# Two_Nine_Five_Rev_1.net
KiCad netlist of a schematic drawn in EAGLE
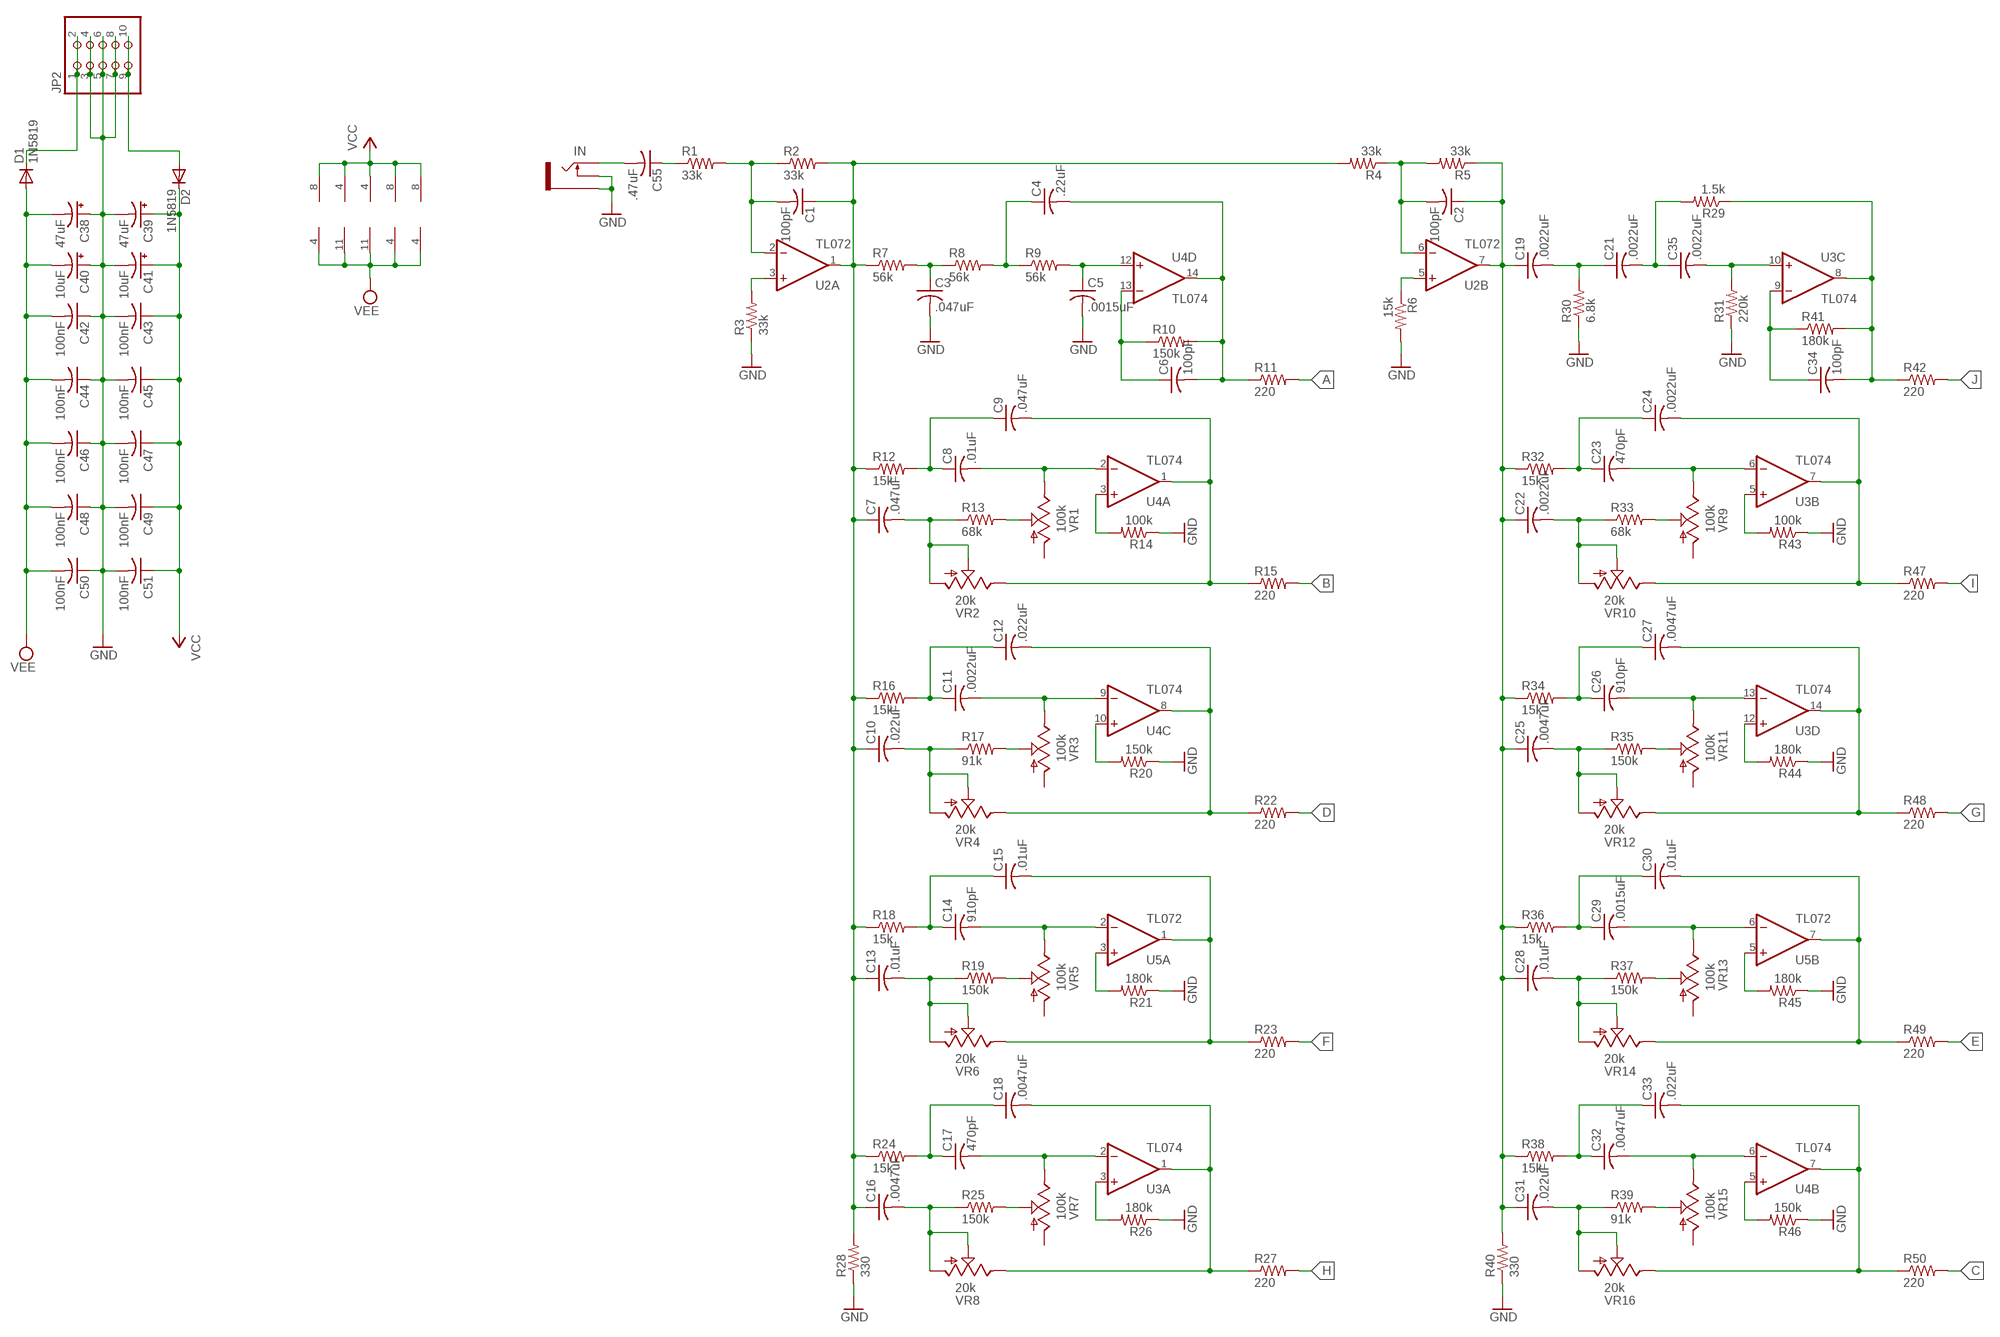
[diagram p0: schematic, sheet 1, part 1 of 2]
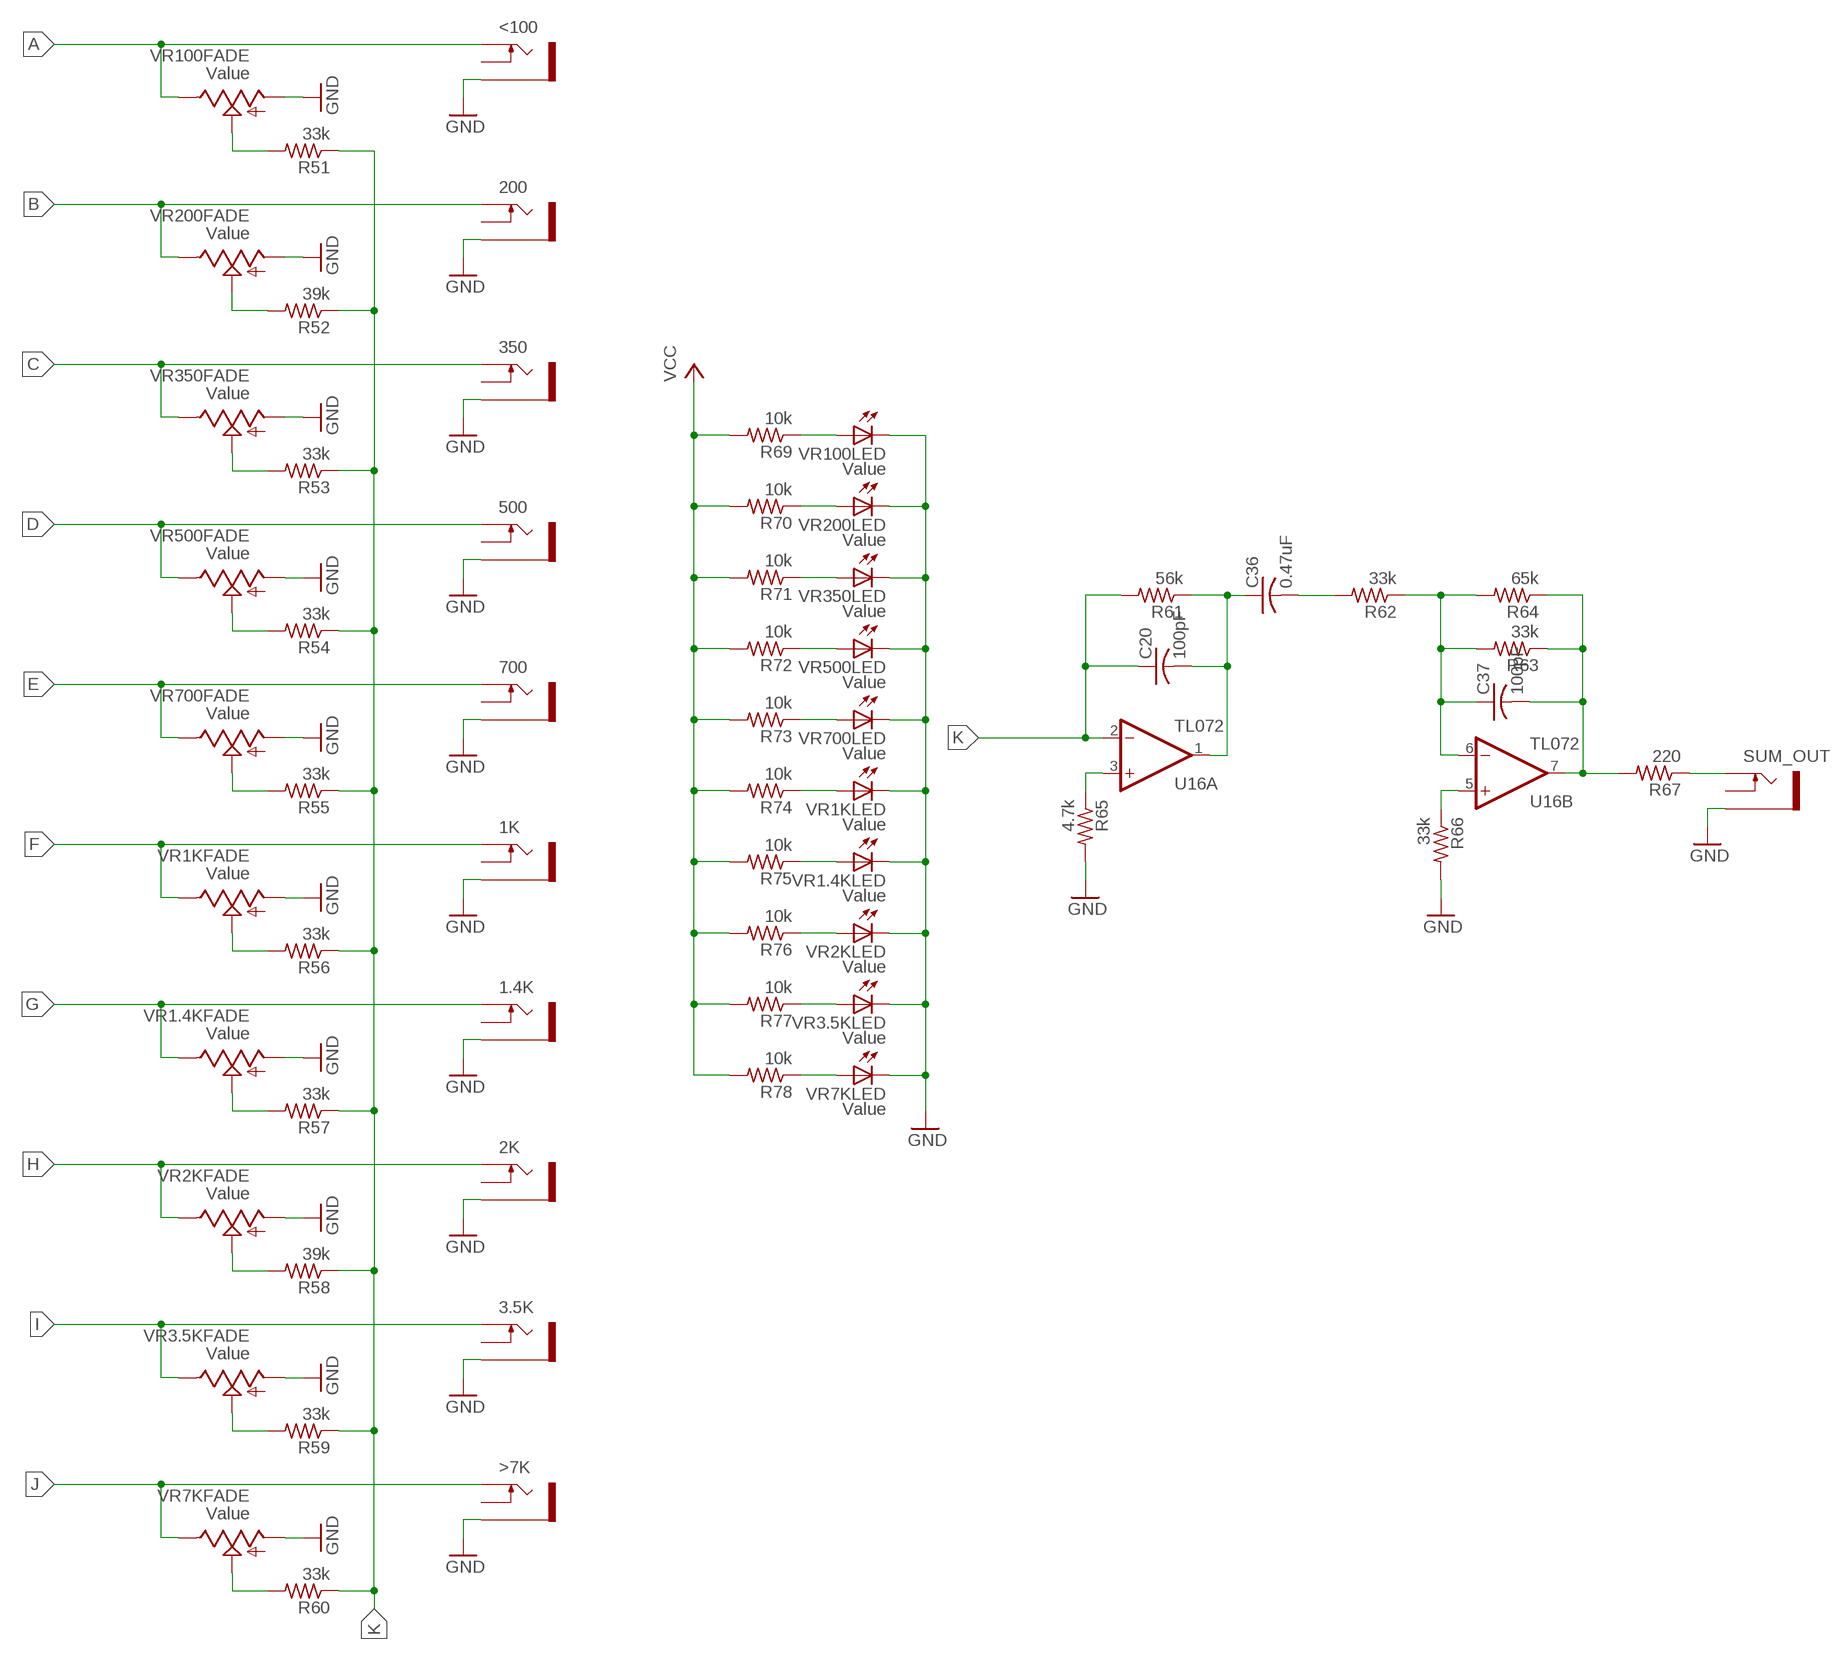
[diagram p1: schematic, sheet 1, part 2 of 2]

(export (version "E")
  (design (tool "Eeschema 10.0.6"))
  (components
    (comp (ref "1.4K")
      (value "THONKICONNNEW")
      (footprint "eagle-import:WQP-PJ301M-12_JACK")
      (libsource (lib "eagle-import") (part "THONKICONNNEW"))
    )
    (comp (ref "1K")
      (value "THONKICONNNEW")
      (footprint "eagle-import:WQP-PJ301M-12_JACK")
      (libsource (lib "eagle-import") (part "THONKICONNNEW"))
    )
    (comp (ref "2K")
      (value "THONKICONNNEW")
      (footprint "eagle-import:WQP-PJ301M-12_JACK")
      (libsource (lib "eagle-import") (part "THONKICONNNEW"))
    )
    (comp (ref "3.5K")
      (value "THONKICONNNEW")
      (footprint "eagle-import:WQP-PJ301M-12_JACK")
      (libsource (lib "eagle-import") (part "THONKICONNNEW"))
    )
    (comp (ref "200")
      (value "THONKICONNNEW")
      (footprint "eagle-import:WQP-PJ301M-12_JACK")
      (libsource (lib "eagle-import") (part "THONKICONNNEW"))
    )
    (comp (ref "350")
      (value "THONKICONNNEW")
      (footprint "eagle-import:WQP-PJ301M-12_JACK")
      (libsource (lib "eagle-import") (part "THONKICONNNEW"))
    )
    (comp (ref "500")
      (value "THONKICONNNEW")
      (footprint "eagle-import:WQP-PJ301M-12_JACK")
      (libsource (lib "eagle-import") (part "THONKICONNNEW"))
    )
    (comp (ref "700")
      (value "THONKICONNNEW")
      (footprint "eagle-import:WQP-PJ301M-12_JACK")
      (libsource (lib "eagle-import") (part "THONKICONNNEW"))
    )
    (comp (ref "<100")
      (value "THONKICONNNEW")
      (footprint "eagle-import:WQP-PJ301M-12_JACK")
      (libsource (lib "eagle-import") (part "THONKICONNNEW"))
    )
    (comp (ref ">7K")
      (value "THONKICONNNEW")
      (footprint "eagle-import:WQP-PJ301M-12_JACK")
      (libsource (lib "eagle-import") (part "THONKICONNNEW"))
    )
    (comp (ref "C1")
      (value "100pF")
      (footprint "eagle-import:C0603")
      (libsource (lib "eagle-import") (part "C-USC0603"))
    )
    (comp (ref "C2")
      (value "100pF")
      (footprint "eagle-import:C0603")
      (libsource (lib "eagle-import") (part "C-USC0603"))
    )
    (comp (ref "C3")
      (value ".047uF")
      (footprint "eagle-import:C0603")
      (libsource (lib "eagle-import") (part "C-USC0603"))
    )
    (comp (ref "C4")
      (value ".22uF")
      (footprint "eagle-import:C0603")
      (libsource (lib "eagle-import") (part "C-USC0603"))
    )
    (comp (ref "C5")
      (value ".0015uF")
      (footprint "eagle-import:C0603")
      (libsource (lib "eagle-import") (part "C-USC0603"))
    )
    (comp (ref "C6")
      (value "100pF")
      (footprint "eagle-import:C0603")
      (libsource (lib "eagle-import") (part "C-USC0603"))
    )
    (comp (ref "C7")
      (value ".047uF")
      (footprint "eagle-import:C0603")
      (libsource (lib "eagle-import") (part "C-USC0603"))
    )
    (comp (ref "C8")
      (value ".01uF")
      (footprint "eagle-import:C0603")
      (libsource (lib "eagle-import") (part "C-USC0603"))
    )
    (comp (ref "C9")
      (value ".047uF")
      (footprint "eagle-import:C0603")
      (libsource (lib "eagle-import") (part "C-USC0603"))
    )
    (comp (ref "C10")
      (value ".022uF")
      (footprint "eagle-import:C0603")
      (libsource (lib "eagle-import") (part "C-USC0603"))
    )
    (comp (ref "C11")
      (value ".0022uF")
      (footprint "eagle-import:C0603")
      (libsource (lib "eagle-import") (part "C-USC0603"))
    )
    (comp (ref "C12")
      (value ".022uF")
      (footprint "eagle-import:C0603")
      (libsource (lib "eagle-import") (part "C-USC0603"))
    )
    (comp (ref "C13")
      (value ".01uF")
      (footprint "eagle-import:C0603")
      (libsource (lib "eagle-import") (part "C-USC0603"))
    )
    (comp (ref "C14")
      (value "910pF")
      (footprint "eagle-import:C0603")
      (libsource (lib "eagle-import") (part "C-USC0603"))
    )
    (comp (ref "C15")
      (value ".01uF")
      (footprint "eagle-import:C0603")
      (libsource (lib "eagle-import") (part "C-USC0603"))
    )
    (comp (ref "C16")
      (value ".0047uF")
      (footprint "eagle-import:C0603")
      (libsource (lib "eagle-import") (part "C-USC0603"))
    )
    (comp (ref "C17")
      (value "470pF")
      (footprint "eagle-import:C0603")
      (libsource (lib "eagle-import") (part "C-USC0603"))
    )
    (comp (ref "C18")
      (value ".0047uF")
      (footprint "eagle-import:C0603")
      (libsource (lib "eagle-import") (part "C-USC0603"))
    )
    (comp (ref "C19")
      (value ".0022uF")
      (footprint "eagle-import:C0603")
      (libsource (lib "eagle-import") (part "C-USC0603"))
    )
    (comp (ref "C20")
      (value "100pF")
      (footprint "eagle-import:C0603")
      (libsource (lib "eagle-import") (part "C-USC0603"))
    )
    (comp (ref "C21")
      (value ".0022uF")
      (footprint "eagle-import:C0603")
      (libsource (lib "eagle-import") (part "C-USC0603"))
    )
    (comp (ref "C22")
      (value ".0022uF")
      (footprint "eagle-import:C0603")
      (libsource (lib "eagle-import") (part "C-USC0603"))
    )
    (comp (ref "C23")
      (value "470pF")
      (footprint "eagle-import:C0603")
      (libsource (lib "eagle-import") (part "C-USC0603"))
    )
    (comp (ref "C24")
      (value ".0022uF")
      (footprint "eagle-import:C0603")
      (libsource (lib "eagle-import") (part "C-USC0603"))
    )
    (comp (ref "C25")
      (value ".0047uF")
      (footprint "eagle-import:C0603")
      (libsource (lib "eagle-import") (part "C-USC0603"))
    )
    (comp (ref "C26")
      (value "910pF")
      (footprint "eagle-import:C0603")
      (libsource (lib "eagle-import") (part "C-USC0603"))
    )
    (comp (ref "C27")
      (value ".0047uF")
      (footprint "eagle-import:C0603")
      (libsource (lib "eagle-import") (part "C-USC0603"))
    )
    (comp (ref "C28")
      (value ".01uF")
      (footprint "eagle-import:C0603")
      (libsource (lib "eagle-import") (part "C-USC0603"))
    )
    (comp (ref "C29")
      (value ".0015uF")
      (footprint "eagle-import:C0603")
      (libsource (lib "eagle-import") (part "C-USC0603"))
    )
    (comp (ref "C30")
      (value ".01uF")
      (footprint "eagle-import:C0603")
      (libsource (lib "eagle-import") (part "C-USC0603"))
    )
    (comp (ref "C31")
      (value ".022uF")
      (footprint "eagle-import:C0603")
      (libsource (lib "eagle-import") (part "C-USC0603"))
    )
    (comp (ref "C32")
      (value ".0047uF")
      (footprint "eagle-import:C0603")
      (libsource (lib "eagle-import") (part "C-USC0603"))
    )
    (comp (ref "C33")
      (value ".022uF")
      (footprint "eagle-import:C0603")
      (libsource (lib "eagle-import") (part "C-USC0603"))
    )
    (comp (ref "C34")
      (value "100pF")
      (footprint "eagle-import:C0603")
      (libsource (lib "eagle-import") (part "C-USC0603"))
    )
    (comp (ref "C35")
      (value ".0022uF")
      (footprint "eagle-import:C0603")
      (libsource (lib "eagle-import") (part "C-USC0603"))
    )
    (comp (ref "C36")
      (value "0.47uF")
      (footprint "eagle-import:C0603")
      (libsource (lib "eagle-import") (part "C-USC0603"))
    )
    (comp (ref "C37")
      (value "100pF")
      (footprint "eagle-import:C0603")
      (libsource (lib "eagle-import") (part "C-USC0603"))
    )
    (comp (ref "C38")
      (value "47uF")
      (footprint "eagle-import:PANASONIC_D")
      (libsource (lib "eagle-import") (part "CPOL-USD"))
    )
    (comp (ref "C39")
      (value "47uF")
      (footprint "eagle-import:PANASONIC_D")
      (libsource (lib "eagle-import") (part "CPOL-USD"))
    )
    (comp (ref "C40")
      (value "10uF")
      (footprint "eagle-import:PANASONIC_B")
      (libsource (lib "eagle-import") (part "CPOL-USB"))
    )
    (comp (ref "C41")
      (value "10uF")
      (footprint "eagle-import:PANASONIC_B")
      (libsource (lib "eagle-import") (part "CPOL-USB"))
    )
    (comp (ref "C42")
      (value "100nF")
      (footprint "eagle-import:C0603")
      (libsource (lib "eagle-import") (part "C-USC0603"))
    )
    (comp (ref "C43")
      (value "100nF")
      (footprint "eagle-import:C0603")
      (libsource (lib "eagle-import") (part "C-USC0603"))
    )
    (comp (ref "C44")
      (value "100nF")
      (footprint "eagle-import:C0603")
      (libsource (lib "eagle-import") (part "C-USC0603"))
    )
    (comp (ref "C45")
      (value "100nF")
      (footprint "eagle-import:C0603")
      (libsource (lib "eagle-import") (part "C-USC0603"))
    )
    (comp (ref "C46")
      (value "100nF")
      (footprint "eagle-import:C0603")
      (libsource (lib "eagle-import") (part "C-USC0603"))
    )
    (comp (ref "C47")
      (value "100nF")
      (footprint "eagle-import:C0603")
      (libsource (lib "eagle-import") (part "C-USC0603"))
    )
    (comp (ref "C48")
      (value "100nF")
      (footprint "eagle-import:C0603")
      (libsource (lib "eagle-import") (part "C-USC0603"))
    )
    (comp (ref "C49")
      (value "100nF")
      (footprint "eagle-import:C0603")
      (libsource (lib "eagle-import") (part "C-USC0603"))
    )
    (comp (ref "C50")
      (value "100nF")
      (footprint "eagle-import:C0603")
      (libsource (lib "eagle-import") (part "C-USC0603"))
    )
    (comp (ref "C51")
      (value "100nF")
      (footprint "eagle-import:C0603")
      (libsource (lib "eagle-import") (part "C-USC0603"))
    )
    (comp (ref "C55")
      (value ".47uF")
      (footprint "eagle-import:C0603")
      (libsource (lib "eagle-import") (part "C-USC0603"))
    )
    (comp (ref "D1")
      (value "1N5819")
      (footprint "eagle-import:SOD123")
      (libsource (lib "eagle-import") (part "DIODE-SOD123"))
    )
    (comp (ref "D2")
      (value "1N5819")
      (footprint "eagle-import:SOD123")
      (libsource (lib "eagle-import") (part "DIODE-SOD123"))
    )
    (comp (ref "IN")
      (value "THONKICONNNEW")
      (footprint "eagle-import:WQP-PJ301M-12_JACK")
      (libsource (lib "eagle-import") (part "THONKICONNNEW"))
    )
    (comp (ref "JP2")
      (value "PINHD-2X5SMT")
      (footprint "eagle-import:2X05_SMT")
      (libsource (lib "eagle-import") (part "PINHD-2X5SMT"))
    )
    (comp (ref "R1")
      (value "33k")
      (footprint "eagle-import:R0603")
      (libsource (lib "eagle-import") (part "R-US_R0603"))
    )
    (comp (ref "R2")
      (value "33k")
      (footprint "eagle-import:R0603")
      (libsource (lib "eagle-import") (part "R-US_R0603"))
    )
    (comp (ref "R3")
      (value "33k")
      (footprint "eagle-import:R0603")
      (libsource (lib "eagle-import") (part "R-US_R0603"))
    )
    (comp (ref "R4")
      (value "33k")
      (footprint "eagle-import:R0603")
      (libsource (lib "eagle-import") (part "R-US_R0603"))
    )
    (comp (ref "R5")
      (value "33k")
      (footprint "eagle-import:R0603")
      (libsource (lib "eagle-import") (part "R-US_R0603"))
    )
    (comp (ref "R6")
      (value "15k")
      (footprint "eagle-import:R0603")
      (libsource (lib "eagle-import") (part "R-US_R0603"))
    )
    (comp (ref "R7")
      (value "56k")
      (footprint "eagle-import:R0603")
      (libsource (lib "eagle-import") (part "R-US_R0603"))
    )
    (comp (ref "R8")
      (value "56k")
      (footprint "eagle-import:R0603")
      (libsource (lib "eagle-import") (part "R-US_R0603"))
    )
    (comp (ref "R9")
      (value "56k")
      (footprint "eagle-import:R0603")
      (libsource (lib "eagle-import") (part "R-US_R0603"))
    )
    (comp (ref "R10")
      (value "150k")
      (footprint "eagle-import:R0603")
      (libsource (lib "eagle-import") (part "R-US_R0603"))
    )
    (comp (ref "R11")
      (value "220")
      (footprint "eagle-import:R0603")
      (libsource (lib "eagle-import") (part "R-US_R0603"))
    )
    (comp (ref "R12")
      (value "15k")
      (footprint "eagle-import:R0603")
      (libsource (lib "eagle-import") (part "R-US_R0603"))
    )
    (comp (ref "R13")
      (value "68k")
      (footprint "eagle-import:R0603")
      (libsource (lib "eagle-import") (part "R-US_R0603"))
    )
    (comp (ref "R14")
      (value "100k")
      (footprint "eagle-import:R0603")
      (libsource (lib "eagle-import") (part "R-US_R0603"))
    )
    (comp (ref "R15")
      (value "220")
      (footprint "eagle-import:R0603")
      (libsource (lib "eagle-import") (part "R-US_R0603"))
    )
    (comp (ref "R16")
      (value "15k")
      (footprint "eagle-import:R0603")
      (libsource (lib "eagle-import") (part "R-US_R0603"))
    )
    (comp (ref "R17")
      (value "91k")
      (footprint "eagle-import:R0603")
      (libsource (lib "eagle-import") (part "R-US_R0603"))
    )
    (comp (ref "R18")
      (value "15k")
      (footprint "eagle-import:R0603")
      (libsource (lib "eagle-import") (part "R-US_R0603"))
    )
    (comp (ref "R19")
      (value "150k")
      (footprint "eagle-import:R0603")
      (libsource (lib "eagle-import") (part "R-US_R0603"))
    )
    (comp (ref "R20")
      (value "150k")
      (footprint "eagle-import:R0603")
      (libsource (lib "eagle-import") (part "R-US_R0603"))
    )
    (comp (ref "R21")
      (value "180k")
      (footprint "eagle-import:R0603")
      (libsource (lib "eagle-import") (part "R-US_R0603"))
    )
    (comp (ref "R22")
      (value "220")
      (footprint "eagle-import:R0603")
      (libsource (lib "eagle-import") (part "R-US_R0603"))
    )
    (comp (ref "R23")
      (value "220")
      (footprint "eagle-import:R0603")
      (libsource (lib "eagle-import") (part "R-US_R0603"))
    )
    (comp (ref "R24")
      (value "15k")
      (footprint "eagle-import:R0603")
      (libsource (lib "eagle-import") (part "R-US_R0603"))
    )
    (comp (ref "R25")
      (value "150k")
      (footprint "eagle-import:R0603")
      (libsource (lib "eagle-import") (part "R-US_R0603"))
    )
    (comp (ref "R26")
      (value "180k")
      (footprint "eagle-import:R0603")
      (libsource (lib "eagle-import") (part "R-US_R0603"))
    )
    (comp (ref "R27")
      (value "220")
      (footprint "eagle-import:R0603")
      (libsource (lib "eagle-import") (part "R-US_R0603"))
    )
    (comp (ref "R28")
      (value "330")
      (footprint "eagle-import:R0603")
      (libsource (lib "eagle-import") (part "R-US_R0603"))
    )
    (comp (ref "R29")
      (value "1.5k")
      (footprint "eagle-import:R0603")
      (libsource (lib "eagle-import") (part "R-US_R0603"))
    )
    (comp (ref "R30")
      (value "6.8k")
      (footprint "eagle-import:R0603")
      (libsource (lib "eagle-import") (part "R-US_R0603"))
    )
    (comp (ref "R31")
      (value "220k")
      (footprint "eagle-import:R0603")
      (libsource (lib "eagle-import") (part "R-US_R0603"))
    )
    (comp (ref "R32")
      (value "15k")
      (footprint "eagle-import:R0603")
      (libsource (lib "eagle-import") (part "R-US_R0603"))
    )
    (comp (ref "R33")
      (value "68k")
      (footprint "eagle-import:R0603")
      (libsource (lib "eagle-import") (part "R-US_R0603"))
    )
    (comp (ref "R34")
      (value "15k")
      (footprint "eagle-import:R0603")
      (libsource (lib "eagle-import") (part "R-US_R0603"))
    )
    (comp (ref "R35")
      (value "150k")
      (footprint "eagle-import:R0603")
      (libsource (lib "eagle-import") (part "R-US_R0603"))
    )
    (comp (ref "R36")
      (value "15k")
      (footprint "eagle-import:R0603")
      (libsource (lib "eagle-import") (part "R-US_R0603"))
    )
    (comp (ref "R37")
      (value "150k")
      (footprint "eagle-import:R0603")
      (libsource (lib "eagle-import") (part "R-US_R0603"))
    )
    (comp (ref "R38")
      (value "15k")
      (footprint "eagle-import:R0603")
      (libsource (lib "eagle-import") (part "R-US_R0603"))
    )
    (comp (ref "R39")
      (value "91k")
      (footprint "eagle-import:R0603")
      (libsource (lib "eagle-import") (part "R-US_R0603"))
    )
    (comp (ref "R40")
      (value "330")
      (footprint "eagle-import:R0603")
      (libsource (lib "eagle-import") (part "R-US_R0603"))
    )
    (comp (ref "R41")
      (value "180k")
      (footprint "eagle-import:R0603")
      (libsource (lib "eagle-import") (part "R-US_R0603"))
    )
    (comp (ref "R42")
      (value "220")
      (footprint "eagle-import:R0603")
      (libsource (lib "eagle-import") (part "R-US_R0603"))
    )
    (comp (ref "R43")
      (value "100k")
      (footprint "eagle-import:R0603")
      (libsource (lib "eagle-import") (part "R-US_R0603"))
    )
    (comp (ref "R44")
      (value "180k")
      (footprint "eagle-import:R0603")
      (libsource (lib "eagle-import") (part "R-US_R0603"))
    )
    (comp (ref "R45")
      (value "180k")
      (footprint "eagle-import:R0603")
      (libsource (lib "eagle-import") (part "R-US_R0603"))
    )
    (comp (ref "R46")
      (value "150k")
      (footprint "eagle-import:R0603")
      (libsource (lib "eagle-import") (part "R-US_R0603"))
    )
    (comp (ref "R47")
      (value "220")
      (footprint "eagle-import:R0603")
      (libsource (lib "eagle-import") (part "R-US_R0603"))
    )
    (comp (ref "R48")
      (value "220")
      (footprint "eagle-import:R0603")
      (libsource (lib "eagle-import") (part "R-US_R0603"))
    )
    (comp (ref "R49")
      (value "220")
      (footprint "eagle-import:R0603")
      (libsource (lib "eagle-import") (part "R-US_R0603"))
    )
    (comp (ref "R50")
      (value "220")
      (footprint "eagle-import:R0603")
      (libsource (lib "eagle-import") (part "R-US_R0603"))
    )
    (comp (ref "R51")
      (value "33k")
      (footprint "eagle-import:R0603")
      (libsource (lib "eagle-import") (part "R-US_R0603"))
    )
    (comp (ref "R52")
      (value "39k")
      (footprint "eagle-import:R0603")
      (libsource (lib "eagle-import") (part "R-US_R0603"))
    )
    (comp (ref "R53")
      (value "33k")
      (footprint "eagle-import:R0603")
      (libsource (lib "eagle-import") (part "R-US_R0603"))
    )
    (comp (ref "R54")
      (value "33k")
      (footprint "eagle-import:R0603")
      (libsource (lib "eagle-import") (part "R-US_R0603"))
    )
    (comp (ref "R55")
      (value "33k")
      (footprint "eagle-import:R0603")
      (libsource (lib "eagle-import") (part "R-US_R0603"))
    )
    (comp (ref "R56")
      (value "33k")
      (footprint "eagle-import:R0603")
      (libsource (lib "eagle-import") (part "R-US_R0603"))
    )
    (comp (ref "R57")
      (value "33k")
      (footprint "eagle-import:R0603")
      (libsource (lib "eagle-import") (part "R-US_R0603"))
    )
    (comp (ref "R58")
      (value "39k")
      (footprint "eagle-import:R0603")
      (libsource (lib "eagle-import") (part "R-US_R0603"))
    )
    (comp (ref "R59")
      (value "33k")
      (footprint "eagle-import:R0603")
      (libsource (lib "eagle-import") (part "R-US_R0603"))
    )
    (comp (ref "R60")
      (value "33k")
      (footprint "eagle-import:R0603")
      (libsource (lib "eagle-import") (part "R-US_R0603"))
    )
    (comp (ref "R61")
      (value "56k")
      (footprint "eagle-import:R0603")
      (libsource (lib "eagle-import") (part "R-US_R0603"))
    )
    (comp (ref "R62")
      (value "33k")
      (footprint "eagle-import:R0603")
      (libsource (lib "eagle-import") (part "R-US_R0603"))
    )
    (comp (ref "R63")
      (value "33k")
      (footprint "eagle-import:R0603")
      (libsource (lib "eagle-import") (part "R-US_R0603"))
    )
    (comp (ref "R64")
      (value "65k")
      (footprint "eagle-import:R0603")
      (libsource (lib "eagle-import") (part "R-US_R0603"))
    )
    (comp (ref "R65")
      (value "4.7k")
      (footprint "eagle-import:R0603")
      (libsource (lib "eagle-import") (part "R-US_R0603"))
    )
    (comp (ref "R66")
      (value "33k")
      (footprint "eagle-import:R0603")
      (libsource (lib "eagle-import") (part "R-US_R0603"))
    )
    (comp (ref "R67")
      (value "220")
      (footprint "eagle-import:R0603")
      (libsource (lib "eagle-import") (part "R-US_R0603"))
    )
    (comp (ref "R69")
      (value "10k")
      (footprint "eagle-import:R0603")
      (libsource (lib "eagle-import") (part "R-US_R0603"))
    )
    (comp (ref "R70")
      (value "10k")
      (footprint "eagle-import:R0603")
      (libsource (lib "eagle-import") (part "R-US_R0603"))
    )
    (comp (ref "R71")
      (value "10k")
      (footprint "eagle-import:R0603")
      (libsource (lib "eagle-import") (part "R-US_R0603"))
    )
    (comp (ref "R72")
      (value "10k")
      (footprint "eagle-import:R0603")
      (libsource (lib "eagle-import") (part "R-US_R0603"))
    )
    (comp (ref "R73")
      (value "10k")
      (footprint "eagle-import:R0603")
      (libsource (lib "eagle-import") (part "R-US_R0603"))
    )
    (comp (ref "R74")
      (value "10k")
      (footprint "eagle-import:R0603")
      (libsource (lib "eagle-import") (part "R-US_R0603"))
    )
    (comp (ref "R75")
      (value "10k")
      (footprint "eagle-import:R0603")
      (libsource (lib "eagle-import") (part "R-US_R0603"))
    )
    (comp (ref "R76")
      (value "10k")
      (footprint "eagle-import:R0603")
      (libsource (lib "eagle-import") (part "R-US_R0603"))
    )
    (comp (ref "R77")
      (value "10k")
      (footprint "eagle-import:R0603")
      (libsource (lib "eagle-import") (part "R-US_R0603"))
    )
    (comp (ref "R78")
      (value "10k")
      (footprint "eagle-import:R0603")
      (libsource (lib "eagle-import") (part "R-US_R0603"))
    )
    (comp (ref "SUM_OUT")
      (value "THONKICONNNEW")
      (footprint "eagle-import:WQP-PJ301M-12_JACK")
      (libsource (lib "eagle-import") (part "THONKICONNNEW"))
    )
    (comp (ref "U2")
      (value "TL072")
      (footprint "eagle-import:SO08")
      (libsource (lib "eagle-import") (part "TL072_SMD"))
    )
    (comp (ref "U3")
      (value "TL074")
      (footprint "eagle-import:SO14")
      (libsource (lib "eagle-import") (part "TL074_SMD"))
    )
    (comp (ref "U4")
      (value "TL074")
      (footprint "eagle-import:SO14")
      (libsource (lib "eagle-import") (part "TL074_SMD"))
    )
    (comp (ref "U5")
      (value "TL072")
      (footprint "eagle-import:SO08")
      (libsource (lib "eagle-import") (part "TL072_SMD"))
    )
    (comp (ref "U16")
      (value "TL072")
      (footprint "eagle-import:SO08")
      (libsource (lib "eagle-import") (part "TL072_SMD"))
    )
    (comp (ref "VR1")
      (value "100k")
      (footprint "eagle-import:RJ9W")
      (libsource (lib "eagle-import") (part "TRIM_US-RJ9W"))
    )
    (comp (ref "VR1.4K")
      (value "Value")
      (footprint "eagle-import:ALPHA_ILL_FADER_20MM_REV2")
      (libsource (lib "eagle-import") (part "ALPHA_20MM_ILLUM_FADER"))
    )
    (comp (ref "VR1K")
      (value "Value")
      (footprint "eagle-import:ALPHA_ILL_FADER_20MM_REV2")
      (libsource (lib "eagle-import") (part "ALPHA_20MM_ILLUM_FADER"))
    )
    (comp (ref "VR2")
      (value "20k")
      (footprint "eagle-import:RJ9W")
      (libsource (lib "eagle-import") (part "TRIM_US-RJ9W"))
    )
    (comp (ref "VR2K")
      (value "Value")
      (footprint "eagle-import:ALPHA_ILL_FADER_20MM_REV2")
      (libsource (lib "eagle-import") (part "ALPHA_20MM_ILLUM_FADER"))
    )
    (comp (ref "VR3")
      (value "100k")
      (footprint "eagle-import:RJ9W")
      (libsource (lib "eagle-import") (part "TRIM_US-RJ9W"))
    )
    (comp (ref "VR3.5K")
      (value "Value")
      (footprint "eagle-import:ALPHA_ILL_FADER_20MM_REV2")
      (libsource (lib "eagle-import") (part "ALPHA_20MM_ILLUM_FADER"))
    )
    (comp (ref "VR4")
      (value "20k")
      (footprint "eagle-import:RJ9W")
      (libsource (lib "eagle-import") (part "TRIM_US-RJ9W"))
    )
    (comp (ref "VR5")
      (value "100k")
      (footprint "eagle-import:RJ9W")
      (libsource (lib "eagle-import") (part "TRIM_US-RJ9W"))
    )
    (comp (ref "VR6")
      (value "20k")
      (footprint "eagle-import:RJ9W")
      (libsource (lib "eagle-import") (part "TRIM_US-RJ9W"))
    )
    (comp (ref "VR7")
      (value "100k")
      (footprint "eagle-import:RJ9W")
      (libsource (lib "eagle-import") (part "TRIM_US-RJ9W"))
    )
    (comp (ref "VR7K")
      (value "Value")
      (footprint "eagle-import:ALPHA_ILL_FADER_20MM_REV2")
      (libsource (lib "eagle-import") (part "ALPHA_20MM_ILLUM_FADER"))
    )
    (comp (ref "VR8")
      (value "20k")
      (footprint "eagle-import:RJ9W")
      (libsource (lib "eagle-import") (part "TRIM_US-RJ9W"))
    )
    (comp (ref "VR9")
      (value "100k")
      (footprint "eagle-import:RJ9W")
      (libsource (lib "eagle-import") (part "TRIM_US-RJ9W"))
    )
    (comp (ref "VR10")
      (value "20k")
      (footprint "eagle-import:RJ9W")
      (libsource (lib "eagle-import") (part "TRIM_US-RJ9W"))
    )
    (comp (ref "VR11")
      (value "100k")
      (footprint "eagle-import:RJ9W")
      (libsource (lib "eagle-import") (part "TRIM_US-RJ9W"))
    )
    (comp (ref "VR12")
      (value "20k")
      (footprint "eagle-import:RJ9W")
      (libsource (lib "eagle-import") (part "TRIM_US-RJ9W"))
    )
    (comp (ref "VR13")
      (value "100k")
      (footprint "eagle-import:RJ9W")
      (libsource (lib "eagle-import") (part "TRIM_US-RJ9W"))
    )
    (comp (ref "VR14")
      (value "20k")
      (footprint "eagle-import:RJ9W")
      (libsource (lib "eagle-import") (part "TRIM_US-RJ9W"))
    )
    (comp (ref "VR15")
      (value "100k")
      (footprint "eagle-import:RJ9W")
      (libsource (lib "eagle-import") (part "TRIM_US-RJ9W"))
    )
    (comp (ref "VR16")
      (value "20k")
      (footprint "eagle-import:RJ9W")
      (libsource (lib "eagle-import") (part "TRIM_US-RJ9W"))
    )
    (comp (ref "VR100")
      (value "Value")
      (footprint "eagle-import:ALPHA_ILL_FADER_20MM_REV2")
      (libsource (lib "eagle-import") (part "ALPHA_20MM_ILLUM_FADER"))
    )
    (comp (ref "VR200")
      (value "Value")
      (footprint "eagle-import:ALPHA_ILL_FADER_20MM_REV2")
      (libsource (lib "eagle-import") (part "ALPHA_20MM_ILLUM_FADER"))
    )
    (comp (ref "VR350")
      (value "Value")
      (footprint "eagle-import:ALPHA_ILL_FADER_20MM_REV2")
      (libsource (lib "eagle-import") (part "ALPHA_20MM_ILLUM_FADER"))
    )
    (comp (ref "VR500")
      (value "Value")
      (footprint "eagle-import:ALPHA_ILL_FADER_20MM_REV2")
      (libsource (lib "eagle-import") (part "ALPHA_20MM_ILLUM_FADER"))
    )
    (comp (ref "VR700")
      (value "Value")
      (footprint "eagle-import:ALPHA_ILL_FADER_20MM_REV2")
      (libsource (lib "eagle-import") (part "ALPHA_20MM_ILLUM_FADER"))
    )
  )
  (nets
    (net (code "1") (name "A") (class "Default")
      (node (ref "<100") (pin "P$1_TIP") (pinfunction "TIP_P$1_TIP") (pintype "passive"))
      (node (ref "R11") (pin "2") (pinfunction "2_2") (pintype "passive"))
      (node (ref "VR100") (pin "1") (pinfunction "E_1") (pintype "passive"))
    )
    (net (code "2") (name "B") (class "Default")
      (node (ref "200") (pin "P$1_TIP") (pinfunction "TIP_P$1_TIP") (pintype "passive"))
      (node (ref "R15") (pin "2") (pinfunction "2_2") (pintype "passive"))
      (node (ref "VR200") (pin "1") (pinfunction "E_1") (pintype "passive"))
    )
    (net (code "3") (name "C") (class "Default")
      (node (ref "350") (pin "P$1_TIP") (pinfunction "TIP_P$1_TIP") (pintype "passive"))
      (node (ref "R50") (pin "2") (pinfunction "2_2") (pintype "passive"))
      (node (ref "VR350") (pin "1") (pinfunction "E_1") (pintype "passive"))
    )
    (net (code "4") (name "D") (class "Default")
      (node (ref "500") (pin "P$1_TIP") (pinfunction "TIP_P$1_TIP") (pintype "passive"))
      (node (ref "R22") (pin "2") (pinfunction "2_2") (pintype "passive"))
      (node (ref "VR500") (pin "1") (pinfunction "E_1") (pintype "passive"))
    )
    (net (code "5") (name "E") (class "Default")
      (node (ref "700") (pin "P$1_TIP") (pinfunction "TIP_P$1_TIP") (pintype "passive"))
      (node (ref "R49") (pin "2") (pinfunction "2_2") (pintype "passive"))
      (node (ref "VR700") (pin "1") (pinfunction "E_1") (pintype "passive"))
    )
    (net (code "6") (name "F") (class "Default")
      (node (ref "1K") (pin "P$1_TIP") (pinfunction "TIP_P$1_TIP") (pintype "passive"))
      (node (ref "R23") (pin "2") (pinfunction "2_2") (pintype "passive"))
      (node (ref "VR1K") (pin "1") (pinfunction "E_1") (pintype "passive"))
    )
    (net (code "7") (name "G") (class "Default")
      (node (ref "1.4K") (pin "P$1_TIP") (pinfunction "TIP_P$1_TIP") (pintype "passive"))
      (node (ref "R48") (pin "2") (pinfunction "2_2") (pintype "passive"))
      (node (ref "VR1.4K") (pin "1") (pinfunction "E_1") (pintype "passive"))
    )
    (net (code "8") (name "GND") (class "Default")
      (node (ref "1.4K") (pin "P$3_SLEEVE") (pinfunction "SLEEVE_P$3_SLEEVE") (pintype "passive"))
      (node (ref "1K") (pin "P$3_SLEEVE") (pinfunction "SLEEVE_P$3_SLEEVE") (pintype "passive"))
      (node (ref "200") (pin "P$3_SLEEVE") (pinfunction "SLEEVE_P$3_SLEEVE") (pintype "passive"))
      (node (ref "2K") (pin "P$3_SLEEVE") (pinfunction "SLEEVE_P$3_SLEEVE") (pintype "passive"))
      (node (ref "3.5K") (pin "P$3_SLEEVE") (pinfunction "SLEEVE_P$3_SLEEVE") (pintype "passive"))
      (node (ref "350") (pin "P$3_SLEEVE") (pinfunction "SLEEVE_P$3_SLEEVE") (pintype "passive"))
      (node (ref "500") (pin "P$3_SLEEVE") (pinfunction "SLEEVE_P$3_SLEEVE") (pintype "passive"))
      (node (ref "700") (pin "P$3_SLEEVE") (pinfunction "SLEEVE_P$3_SLEEVE") (pintype "passive"))
      (node (ref "<100") (pin "P$3_SLEEVE") (pinfunction "SLEEVE_P$3_SLEEVE") (pintype "passive"))
      (node (ref ">7K") (pin "P$3_SLEEVE") (pinfunction "SLEEVE_P$3_SLEEVE") (pintype "passive"))
      (node (ref "C3") (pin "2") (pinfunction "2_2") (pintype "passive"))
      (node (ref "C38") (pin "+") (pinfunction "+_+") (pintype "passive"))
      (node (ref "C39") (pin "-") (pinfunction "-_-") (pintype "passive"))
      (node (ref "C40") (pin "+") (pinfunction "+_+") (pintype "passive"))
      (node (ref "C41") (pin "-") (pinfunction "-_-") (pintype "passive"))
      (node (ref "C42") (pin "1") (pinfunction "1_1") (pintype "passive"))
      (node (ref "C43") (pin "2") (pinfunction "2_2") (pintype "passive"))
      (node (ref "C44") (pin "1") (pinfunction "1_1") (pintype "passive"))
      (node (ref "C45") (pin "2") (pinfunction "2_2") (pintype "passive"))
      (node (ref "C46") (pin "1") (pinfunction "1_1") (pintype "passive"))
      (node (ref "C47") (pin "2") (pinfunction "2_2") (pintype "passive"))
      (node (ref "C48") (pin "1") (pinfunction "1_1") (pintype "passive"))
      (node (ref "C49") (pin "2") (pinfunction "2_2") (pintype "passive"))
      (node (ref "C5") (pin "2") (pinfunction "2_2") (pintype "passive"))
      (node (ref "C50") (pin "1") (pinfunction "1_1") (pintype "passive"))
      (node (ref "C51") (pin "2") (pinfunction "2_2") (pintype "passive"))
      (node (ref "IN") (pin "P$2_SWITCH") (pinfunction "SWITCH_P$2_SWITCH") (pintype "passive"))
      (node (ref "IN") (pin "P$3_SLEEVE") (pinfunction "SLEEVE_P$3_SLEEVE") (pintype "passive"))
      (node (ref "JP2") (pin "3") (pinfunction "3_3") (pintype "passive"))
      (node (ref "JP2") (pin "4") (pinfunction "4_4") (pintype "passive"))
      (node (ref "JP2") (pin "5") (pinfunction "5_5") (pintype "passive"))
      (node (ref "JP2") (pin "6") (pinfunction "6_6") (pintype "passive"))
      (node (ref "JP2") (pin "7") (pinfunction "7_7") (pintype "passive"))
      (node (ref "JP2") (pin "8") (pinfunction "8_8") (pintype "passive"))
      (node (ref "R14") (pin "1") (pinfunction "1_1") (pintype "passive"))
      (node (ref "R20") (pin "1") (pinfunction "1_1") (pintype "passive"))
      (node (ref "R21") (pin "1") (pinfunction "1_1") (pintype "passive"))
      (node (ref "R26") (pin "1") (pinfunction "1_1") (pintype "passive"))
      (node (ref "R28") (pin "1") (pinfunction "1_1") (pintype "passive"))
      (node (ref "R3") (pin "1") (pinfunction "1_1") (pintype "passive"))
      (node (ref "R30") (pin "1") (pinfunction "1_1") (pintype "passive"))
      (node (ref "R31") (pin "1") (pinfunction "1_1") (pintype "passive"))
      (node (ref "R40") (pin "1") (pinfunction "1_1") (pintype "passive"))
      (node (ref "R43") (pin "1") (pinfunction "1_1") (pintype "passive"))
      (node (ref "R44") (pin "1") (pinfunction "1_1") (pintype "passive"))
      (node (ref "R45") (pin "1") (pinfunction "1_1") (pintype "passive"))
      (node (ref "R46") (pin "1") (pinfunction "1_1") (pintype "passive"))
      (node (ref "R6") (pin "2") (pinfunction "2_2") (pintype "passive"))
      (node (ref "R65") (pin "2") (pinfunction "2_2") (pintype "passive"))
      (node (ref "R66") (pin "2") (pinfunction "2_2") (pintype "passive"))
      (node (ref "SUM_OUT") (pin "P$3_SLEEVE") (pinfunction "SLEEVE_P$3_SLEEVE") (pintype "passive"))
      (node (ref "VR1.4K") (pin "3") (pinfunction "A_3") (pintype "passive"))
      (node (ref "VR1.4K") (pin "E") (pinfunction "C_E") (pintype "passive"))
      (node (ref "VR100") (pin "3") (pinfunction "A_3") (pintype "passive"))
      (node (ref "VR100") (pin "E") (pinfunction "C_E") (pintype "passive"))
      (node (ref "VR1K") (pin "3") (pinfunction "A_3") (pintype "passive"))
      (node (ref "VR1K") (pin "E") (pinfunction "C_E") (pintype "passive"))
      (node (ref "VR200") (pin "3") (pinfunction "A_3") (pintype "passive"))
      (node (ref "VR200") (pin "E") (pinfunction "C_E") (pintype "passive"))
      (node (ref "VR2K") (pin "3") (pinfunction "A_3") (pintype "passive"))
      (node (ref "VR2K") (pin "E") (pinfunction "C_E") (pintype "passive"))
      (node (ref "VR3.5K") (pin "3") (pinfunction "A_3") (pintype "passive"))
      (node (ref "VR3.5K") (pin "E") (pinfunction "C_E") (pintype "passive"))
      (node (ref "VR350") (pin "3") (pinfunction "A_3") (pintype "passive"))
      (node (ref "VR350") (pin "E") (pinfunction "C_E") (pintype "passive"))
      (node (ref "VR500") (pin "3") (pinfunction "A_3") (pintype "passive"))
      (node (ref "VR500") (pin "E") (pinfunction "C_E") (pintype "passive"))
      (node (ref "VR700") (pin "3") (pinfunction "A_3") (pintype "passive"))
      (node (ref "VR700") (pin "E") (pinfunction "C_E") (pintype "passive"))
      (node (ref "VR7K") (pin "3") (pinfunction "A_3") (pintype "passive"))
      (node (ref "VR7K") (pin "E") (pinfunction "C_E") (pintype "passive"))
    )
    (net (code "9") (name "H") (class "Default")
      (node (ref "2K") (pin "P$1_TIP") (pinfunction "TIP_P$1_TIP") (pintype "passive"))
      (node (ref "R27") (pin "2") (pinfunction "2_2") (pintype "passive"))
      (node (ref "VR2K") (pin "1") (pinfunction "E_1") (pintype "passive"))
    )
    (net (code "10") (name "I") (class "Default")
      (node (ref "3.5K") (pin "P$1_TIP") (pinfunction "TIP_P$1_TIP") (pintype "passive"))
      (node (ref "R47") (pin "2") (pinfunction "2_2") (pintype "passive"))
      (node (ref "VR3.5K") (pin "1") (pinfunction "E_1") (pintype "passive"))
    )
    (net (code "11") (name "J") (class "Default")
      (node (ref ">7K") (pin "P$1_TIP") (pinfunction "TIP_P$1_TIP") (pintype "passive"))
      (node (ref "R42") (pin "2") (pinfunction "2_2") (pintype "passive"))
      (node (ref "VR7K") (pin "1") (pinfunction "E_1") (pintype "passive"))
    )
    (net (code "12") (name "K") (class "Default")
      (node (ref "C20") (pin "1") (pinfunction "1_1") (pintype "passive"))
      (node (ref "R51") (pin "1") (pinfunction "1_1") (pintype "passive"))
      (node (ref "R52") (pin "1") (pinfunction "1_1") (pintype "passive"))
      (node (ref "R53") (pin "1") (pinfunction "1_1") (pintype "passive"))
      (node (ref "R54") (pin "1") (pinfunction "1_1") (pintype "passive"))
      (node (ref "R55") (pin "1") (pinfunction "1_1") (pintype "passive"))
      (node (ref "R56") (pin "1") (pinfunction "1_1") (pintype "passive"))
      (node (ref "R57") (pin "1") (pinfunction "1_1") (pintype "passive"))
      (node (ref "R58") (pin "1") (pinfunction "1_1") (pintype "passive"))
      (node (ref "R59") (pin "1") (pinfunction "1_1") (pintype "passive"))
      (node (ref "R60") (pin "1") (pinfunction "1_1") (pintype "passive"))
      (node (ref "R61") (pin "2") (pinfunction "2_2") (pintype "passive"))
      (node (ref "U16") (pin "2") (pinfunction "-IN_2") (pintype "input"))
    )
    (net (code "13") (name "Net-(C3-Pad1)") (class "Default")
      (node (ref "C3") (pin "1") (pinfunction "1_1") (pintype "passive"))
      (node (ref "R7") (pin "2") (pinfunction "2_2") (pintype "passive"))
      (node (ref "R8") (pin "1") (pinfunction "1_1") (pintype "passive"))
    )
    (net (code "14") (name "Net-(C4-Pad1)") (class "Default")
      (node (ref "C4") (pin "1") (pinfunction "1_1") (pintype "passive"))
      (node (ref "R8") (pin "2") (pinfunction "2_2") (pintype "passive"))
      (node (ref "R9") (pin "1") (pinfunction "1_1") (pintype "passive"))
    )
    (net (code "15") (name "Net-(C7-Pad2)") (class "Default")
      (node (ref "C7") (pin "2") (pinfunction "2_2") (pintype "passive"))
      (node (ref "R13") (pin "1") (pinfunction "1_1") (pintype "passive"))
      (node (ref "VR2") (pin "A") (pinfunction "A_A") (pintype "passive"))
      (node (ref "VR2") (pin "S") (pinfunction "S_S") (pintype "passive"))
    )
    (net (code "16") (name "Net-(C8-Pad1)") (class "Default")
      (node (ref "C8") (pin "1") (pinfunction "1_1") (pintype "passive"))
      (node (ref "C9") (pin "1") (pinfunction "1_1") (pintype "passive"))
      (node (ref "R12") (pin "2") (pinfunction "2_2") (pintype "passive"))
    )
    (net (code "17") (name "Net-(C10-Pad2)") (class "Default")
      (node (ref "C10") (pin "2") (pinfunction "2_2") (pintype "passive"))
      (node (ref "R17") (pin "1") (pinfunction "1_1") (pintype "passive"))
      (node (ref "VR4") (pin "A") (pinfunction "A_A") (pintype "passive"))
      (node (ref "VR4") (pin "S") (pinfunction "S_S") (pintype "passive"))
    )
    (net (code "18") (name "Net-(C11-Pad1)") (class "Default")
      (node (ref "C11") (pin "1") (pinfunction "1_1") (pintype "passive"))
      (node (ref "C12") (pin "1") (pinfunction "1_1") (pintype "passive"))
      (node (ref "R16") (pin "2") (pinfunction "2_2") (pintype "passive"))
    )
    (net (code "19") (name "Net-(C13-Pad2)") (class "Default")
      (node (ref "C13") (pin "2") (pinfunction "2_2") (pintype "passive"))
      (node (ref "R19") (pin "1") (pinfunction "1_1") (pintype "passive"))
      (node (ref "VR6") (pin "A") (pinfunction "A_A") (pintype "passive"))
      (node (ref "VR6") (pin "S") (pinfunction "S_S") (pintype "passive"))
    )
    (net (code "20") (name "Net-(C14-Pad1)") (class "Default")
      (node (ref "C14") (pin "1") (pinfunction "1_1") (pintype "passive"))
      (node (ref "C15") (pin "1") (pinfunction "1_1") (pintype "passive"))
      (node (ref "R18") (pin "2") (pinfunction "2_2") (pintype "passive"))
    )
    (net (code "21") (name "Net-(C16-Pad2)") (class "Default")
      (node (ref "C16") (pin "2") (pinfunction "2_2") (pintype "passive"))
      (node (ref "R25") (pin "1") (pinfunction "1_1") (pintype "passive"))
      (node (ref "VR8") (pin "A") (pinfunction "A_A") (pintype "passive"))
      (node (ref "VR8") (pin "S") (pinfunction "S_S") (pintype "passive"))
    )
    (net (code "22") (name "Net-(C17-Pad1)") (class "Default")
      (node (ref "C17") (pin "1") (pinfunction "1_1") (pintype "passive"))
      (node (ref "C18") (pin "1") (pinfunction "1_1") (pintype "passive"))
      (node (ref "R24") (pin "2") (pinfunction "2_2") (pintype "passive"))
    )
    (net (code "23") (name "Net-(C19-Pad2)") (class "Default")
      (node (ref "C19") (pin "2") (pinfunction "2_2") (pintype "passive"))
      (node (ref "C21") (pin "1") (pinfunction "1_1") (pintype "passive"))
      (node (ref "R30") (pin "2") (pinfunction "2_2") (pintype "passive"))
    )
    (net (code "24") (name "Net-(C21-Pad2)") (class "Default")
      (node (ref "C21") (pin "2") (pinfunction "2_2") (pintype "passive"))
      (node (ref "C35") (pin "1") (pinfunction "1_1") (pintype "passive"))
      (node (ref "R29") (pin "2") (pinfunction "2_2") (pintype "passive"))
    )
    (net (code "25") (name "Net-(C22-Pad2)") (class "Default")
      (node (ref "C22") (pin "2") (pinfunction "2_2") (pintype "passive"))
      (node (ref "R33") (pin "1") (pinfunction "1_1") (pintype "passive"))
      (node (ref "VR10") (pin "A") (pinfunction "A_A") (pintype "passive"))
      (node (ref "VR10") (pin "S") (pinfunction "S_S") (pintype "passive"))
    )
    (net (code "26") (name "Net-(C23-Pad1)") (class "Default")
      (node (ref "C23") (pin "1") (pinfunction "1_1") (pintype "passive"))
      (node (ref "C24") (pin "1") (pinfunction "1_1") (pintype "passive"))
      (node (ref "R32") (pin "2") (pinfunction "2_2") (pintype "passive"))
    )
    (net (code "27") (name "Net-(C25-Pad2)") (class "Default")
      (node (ref "C25") (pin "2") (pinfunction "2_2") (pintype "passive"))
      (node (ref "R35") (pin "1") (pinfunction "1_1") (pintype "passive"))
      (node (ref "VR12") (pin "A") (pinfunction "A_A") (pintype "passive"))
      (node (ref "VR12") (pin "S") (pinfunction "S_S") (pintype "passive"))
    )
    (net (code "28") (name "Net-(C26-Pad1)") (class "Default")
      (node (ref "C26") (pin "1") (pinfunction "1_1") (pintype "passive"))
      (node (ref "C27") (pin "1") (pinfunction "1_1") (pintype "passive"))
      (node (ref "R34") (pin "2") (pinfunction "2_2") (pintype "passive"))
    )
    (net (code "29") (name "Net-(C28-Pad2)") (class "Default")
      (node (ref "C28") (pin "2") (pinfunction "2_2") (pintype "passive"))
      (node (ref "R37") (pin "1") (pinfunction "1_1") (pintype "passive"))
      (node (ref "VR14") (pin "A") (pinfunction "A_A") (pintype "passive"))
      (node (ref "VR14") (pin "S") (pinfunction "S_S") (pintype "passive"))
    )
    (net (code "30") (name "Net-(C29-Pad1)") (class "Default")
      (node (ref "C29") (pin "1") (pinfunction "1_1") (pintype "passive"))
      (node (ref "C30") (pin "1") (pinfunction "1_1") (pintype "passive"))
      (node (ref "R36") (pin "2") (pinfunction "2_2") (pintype "passive"))
    )
    (net (code "31") (name "Net-(C31-Pad2)") (class "Default")
      (node (ref "C31") (pin "2") (pinfunction "2_2") (pintype "passive"))
      (node (ref "R39") (pin "1") (pinfunction "1_1") (pintype "passive"))
      (node (ref "VR16") (pin "A") (pinfunction "A_A") (pintype "passive"))
      (node (ref "VR16") (pin "S") (pinfunction "S_S") (pintype "passive"))
    )
    (net (code "32") (name "Net-(C32-Pad1)") (class "Default")
      (node (ref "C32") (pin "1") (pinfunction "1_1") (pintype "passive"))
      (node (ref "C33") (pin "1") (pinfunction "1_1") (pintype "passive"))
      (node (ref "R38") (pin "2") (pinfunction "2_2") (pintype "passive"))
    )
    (net (code "33") (name "Net-(C36-Pad2)") (class "Default")
      (node (ref "C36") (pin "2") (pinfunction "2_2") (pintype "passive"))
      (node (ref "R62") (pin "2") (pinfunction "2_2") (pintype "passive"))
    )
    (net (code "34") (name "Net-(C55-Pad1)") (class "Default")
      (node (ref "C55") (pin "1") (pinfunction "1_1") (pintype "passive"))
      (node (ref "R1") (pin "1") (pinfunction "1_1") (pintype "passive"))
    )
    (net (code "35") (name "Net-(D1-PadC)") (class "Default")
      (node (ref "D1") (pin "C") (pinfunction "C_C") (pintype "passive"))
      (node (ref "JP2") (pin "1") (pinfunction "1_1") (pintype "passive"))
      (node (ref "JP2") (pin "2") (pinfunction "2_2") (pintype "passive"))
    )
    (net (code "36") (name "Net-(D2-PadA)") (class "Default")
      (node (ref "D2") (pin "A") (pinfunction "A_A") (pintype "passive"))
      (node (ref "JP2") (pin "10") (pinfunction "10_10") (pintype "passive"))
      (node (ref "JP2") (pin "9") (pinfunction "9_9") (pintype "passive"))
    )
    (net (code "37") (name "Net-(IN-TIP)") (class "Default")
      (node (ref "C55") (pin "2") (pinfunction "2_2") (pintype "passive"))
      (node (ref "IN") (pin "P$1_TIP") (pinfunction "TIP_P$1_TIP") (pintype "passive"))
    )
    (net (code "38") (name "Net-(R13-Pad2)") (class "Default")
      (node (ref "R13") (pin "2") (pinfunction "2_2") (pintype "passive"))
      (node (ref "VR1") (pin "S") (pinfunction "S_S") (pintype "passive"))
    )
    (net (code "39") (name "Net-(R17-Pad2)") (class "Default")
      (node (ref "R17") (pin "2") (pinfunction "2_2") (pintype "passive"))
      (node (ref "VR3") (pin "S") (pinfunction "S_S") (pintype "passive"))
    )
    (net (code "40") (name "Net-(R19-Pad2)") (class "Default")
      (node (ref "R19") (pin "2") (pinfunction "2_2") (pintype "passive"))
      (node (ref "VR5") (pin "S") (pinfunction "S_S") (pintype "passive"))
    )
    (net (code "41") (name "Net-(R25-Pad2)") (class "Default")
      (node (ref "R25") (pin "2") (pinfunction "2_2") (pintype "passive"))
      (node (ref "VR7") (pin "S") (pinfunction "S_S") (pintype "passive"))
    )
    (net (code "42") (name "Net-(R33-Pad2)") (class "Default")
      (node (ref "R33") (pin "2") (pinfunction "2_2") (pintype "passive"))
      (node (ref "VR9") (pin "S") (pinfunction "S_S") (pintype "passive"))
    )
    (net (code "43") (name "Net-(R35-Pad2)") (class "Default")
      (node (ref "R35") (pin "2") (pinfunction "2_2") (pintype "passive"))
      (node (ref "VR11") (pin "S") (pinfunction "S_S") (pintype "passive"))
    )
    (net (code "44") (name "Net-(R37-Pad2)") (class "Default")
      (node (ref "R37") (pin "2") (pinfunction "2_2") (pintype "passive"))
      (node (ref "VR13") (pin "S") (pinfunction "S_S") (pintype "passive"))
    )
    (net (code "45") (name "Net-(R39-Pad2)") (class "Default")
      (node (ref "R39") (pin "2") (pinfunction "2_2") (pintype "passive"))
      (node (ref "VR15") (pin "S") (pinfunction "S_S") (pintype "passive"))
    )
    (net (code "46") (name "Net-(SUM_OUT-TIP)") (class "Default")
      (node (ref "R67") (pin "1") (pinfunction "1_1") (pintype "passive"))
      (node (ref "SUM_OUT") (pin "P$1_TIP") (pinfunction "TIP_P$1_TIP") (pintype "passive"))
    )
    (net (code "47") (name "Net-(U2A-+IN)") (class "Default")
      (node (ref "R3") (pin "2") (pinfunction "2_2") (pintype "passive"))
      (node (ref "U2") (pin "3") (pinfunction "+IN_3") (pintype "input"))
    )
    (net (code "48") (name "Net-(U2A--IN)") (class "Default")
      (node (ref "C1") (pin "2") (pinfunction "2_2") (pintype "passive"))
      (node (ref "R1") (pin "2") (pinfunction "2_2") (pintype "passive"))
      (node (ref "R2") (pin "1") (pinfunction "1_1") (pintype "passive"))
      (node (ref "U2") (pin "2") (pinfunction "-IN_2") (pintype "input"))
    )
    (net (code "49") (name "Net-(U2A-OUT)") (class "Default")
      (node (ref "C1") (pin "1") (pinfunction "1_1") (pintype "passive"))
      (node (ref "C10") (pin "1") (pinfunction "1_1") (pintype "passive"))
      (node (ref "C13") (pin "1") (pinfunction "1_1") (pintype "passive"))
      (node (ref "C16") (pin "1") (pinfunction "1_1") (pintype "passive"))
      (node (ref "C7") (pin "1") (pinfunction "1_1") (pintype "passive"))
      (node (ref "R12") (pin "1") (pinfunction "1_1") (pintype "passive"))
      (node (ref "R16") (pin "1") (pinfunction "1_1") (pintype "passive"))
      (node (ref "R18") (pin "1") (pinfunction "1_1") (pintype "passive"))
      (node (ref "R2") (pin "2") (pinfunction "2_2") (pintype "passive"))
      (node (ref "R24") (pin "1") (pinfunction "1_1") (pintype "passive"))
      (node (ref "R28") (pin "2") (pinfunction "2_2") (pintype "passive"))
      (node (ref "R4") (pin "2") (pinfunction "2_2") (pintype "passive"))
      (node (ref "R7") (pin "1") (pinfunction "1_1") (pintype "passive"))
      (node (ref "U2") (pin "1") (pinfunction "OUT_1") (pintype "output"))
    )
    (net (code "50") (name "Net-(U2B-+IN)") (class "Default")
      (node (ref "R6") (pin "1") (pinfunction "1_1") (pintype "passive"))
      (node (ref "U2") (pin "5") (pinfunction "+IN_5") (pintype "input"))
    )
    (net (code "51") (name "Net-(U2B--IN)") (class "Default")
      (node (ref "C2") (pin "2") (pinfunction "2_2") (pintype "passive"))
      (node (ref "R4") (pin "1") (pinfunction "1_1") (pintype "passive"))
      (node (ref "R5") (pin "2") (pinfunction "2_2") (pintype "passive"))
      (node (ref "U2") (pin "6") (pinfunction "-IN_6") (pintype "input"))
    )
    (net (code "52") (name "Net-(U2B-OUT)") (class "Default")
      (node (ref "C19") (pin "1") (pinfunction "1_1") (pintype "passive"))
      (node (ref "C2") (pin "1") (pinfunction "1_1") (pintype "passive"))
      (node (ref "C22") (pin "1") (pinfunction "1_1") (pintype "passive"))
      (node (ref "C25") (pin "1") (pinfunction "1_1") (pintype "passive"))
      (node (ref "C28") (pin "1") (pinfunction "1_1") (pintype "passive"))
      (node (ref "C31") (pin "1") (pinfunction "1_1") (pintype "passive"))
      (node (ref "R32") (pin "1") (pinfunction "1_1") (pintype "passive"))
      (node (ref "R34") (pin "1") (pinfunction "1_1") (pintype "passive"))
      (node (ref "R36") (pin "1") (pinfunction "1_1") (pintype "passive"))
      (node (ref "R38") (pin "1") (pinfunction "1_1") (pintype "passive"))
      (node (ref "R40") (pin "2") (pinfunction "2_2") (pintype "passive"))
      (node (ref "R5") (pin "1") (pinfunction "1_1") (pintype "passive"))
      (node (ref "U2") (pin "7") (pinfunction "OUT_7") (pintype "output"))
    )
    (net (code "53") (name "Net-(U3A-+IN)") (class "Default")
      (node (ref "R26") (pin "2") (pinfunction "2_2") (pintype "passive"))
      (node (ref "U3") (pin "3") (pinfunction "+IN_3") (pintype "input"))
    )
    (net (code "54") (name "Net-(U3A--IN)") (class "Default")
      (node (ref "C17") (pin "2") (pinfunction "2_2") (pintype "passive"))
      (node (ref "U3") (pin "2") (pinfunction "-IN_2") (pintype "input"))
      (node (ref "VR7") (pin "E") (pinfunction "E_E") (pintype "passive"))
    )
    (net (code "55") (name "Net-(U3A-OUT)") (class "Default")
      (node (ref "C18") (pin "2") (pinfunction "2_2") (pintype "passive"))
      (node (ref "R27") (pin "1") (pinfunction "1_1") (pintype "passive"))
      (node (ref "U3") (pin "1") (pinfunction "OUT_1") (pintype "output"))
      (node (ref "VR8") (pin "E") (pinfunction "E_E") (pintype "passive"))
    )
    (net (code "56") (name "Net-(U3B-+IN)") (class "Default")
      (node (ref "R43") (pin "2") (pinfunction "2_2") (pintype "passive"))
      (node (ref "U3") (pin "5") (pinfunction "+IN_5") (pintype "input"))
    )
    (net (code "57") (name "Net-(U3B--IN)") (class "Default")
      (node (ref "C23") (pin "2") (pinfunction "2_2") (pintype "passive"))
      (node (ref "U3") (pin "6") (pinfunction "-IN_6") (pintype "input"))
      (node (ref "VR9") (pin "E") (pinfunction "E_E") (pintype "passive"))
    )
    (net (code "58") (name "Net-(U3B-OUT)") (class "Default")
      (node (ref "C24") (pin "2") (pinfunction "2_2") (pintype "passive"))
      (node (ref "R47") (pin "1") (pinfunction "1_1") (pintype "passive"))
      (node (ref "U3") (pin "7") (pinfunction "OUT_7") (pintype "output"))
      (node (ref "VR10") (pin "E") (pinfunction "E_E") (pintype "passive"))
    )
    (net (code "59") (name "Net-(U3C-+IN)") (class "Default")
      (node (ref "C35") (pin "2") (pinfunction "2_2") (pintype "passive"))
      (node (ref "R31") (pin "2") (pinfunction "2_2") (pintype "passive"))
      (node (ref "U3") (pin "10") (pinfunction "+IN_10") (pintype "input"))
    )
    (net (code "60") (name "Net-(U3C--IN)") (class "Default")
      (node (ref "C34") (pin "1") (pinfunction "1_1") (pintype "passive"))
      (node (ref "R41") (pin "1") (pinfunction "1_1") (pintype "passive"))
      (node (ref "U3") (pin "9") (pinfunction "-IN_9") (pintype "input"))
    )
    (net (code "61") (name "Net-(U3C-OUT)") (class "Default")
      (node (ref "C34") (pin "2") (pinfunction "2_2") (pintype "passive"))
      (node (ref "R29") (pin "1") (pinfunction "1_1") (pintype "passive"))
      (node (ref "R41") (pin "2") (pinfunction "2_2") (pintype "passive"))
      (node (ref "R42") (pin "1") (pinfunction "1_1") (pintype "passive"))
      (node (ref "U3") (pin "8") (pinfunction "OUT_8") (pintype "output"))
    )
    (net (code "62") (name "Net-(U3D-+IN)") (class "Default")
      (node (ref "R44") (pin "2") (pinfunction "2_2") (pintype "passive"))
      (node (ref "U3") (pin "12") (pinfunction "+IN_12") (pintype "input"))
    )
    (net (code "63") (name "Net-(U3D--IN)") (class "Default")
      (node (ref "C26") (pin "2") (pinfunction "2_2") (pintype "passive"))
      (node (ref "U3") (pin "13") (pinfunction "-IN_13") (pintype "input"))
      (node (ref "VR11") (pin "E") (pinfunction "E_E") (pintype "passive"))
    )
    (net (code "64") (name "Net-(U3D-OUT)") (class "Default")
      (node (ref "C27") (pin "2") (pinfunction "2_2") (pintype "passive"))
      (node (ref "R48") (pin "1") (pinfunction "1_1") (pintype "passive"))
      (node (ref "U3") (pin "14") (pinfunction "OUT_14") (pintype "output"))
      (node (ref "VR12") (pin "E") (pinfunction "E_E") (pintype "passive"))
    )
    (net (code "65") (name "Net-(U4A-+IN)") (class "Default")
      (node (ref "R14") (pin "2") (pinfunction "2_2") (pintype "passive"))
      (node (ref "U4") (pin "3") (pinfunction "+IN_3") (pintype "input"))
    )
    (net (code "66") (name "Net-(U4A--IN)") (class "Default")
      (node (ref "C8") (pin "2") (pinfunction "2_2") (pintype "passive"))
      (node (ref "U4") (pin "2") (pinfunction "-IN_2") (pintype "input"))
      (node (ref "VR1") (pin "E") (pinfunction "E_E") (pintype "passive"))
    )
    (net (code "67") (name "Net-(U4A-OUT)") (class "Default")
      (node (ref "C9") (pin "2") (pinfunction "2_2") (pintype "passive"))
      (node (ref "R15") (pin "1") (pinfunction "1_1") (pintype "passive"))
      (node (ref "U4") (pin "1") (pinfunction "OUT_1") (pintype "output"))
      (node (ref "VR2") (pin "E") (pinfunction "E_E") (pintype "passive"))
    )
    (net (code "68") (name "Net-(U4B-+IN)") (class "Default")
      (node (ref "R46") (pin "2") (pinfunction "2_2") (pintype "passive"))
      (node (ref "U4") (pin "5") (pinfunction "+IN_5") (pintype "input"))
    )
    (net (code "69") (name "Net-(U4B--IN)") (class "Default")
      (node (ref "C32") (pin "2") (pinfunction "2_2") (pintype "passive"))
      (node (ref "U4") (pin "6") (pinfunction "-IN_6") (pintype "input"))
      (node (ref "VR15") (pin "E") (pinfunction "E_E") (pintype "passive"))
    )
    (net (code "70") (name "Net-(U4B-OUT)") (class "Default")
      (node (ref "C33") (pin "2") (pinfunction "2_2") (pintype "passive"))
      (node (ref "R50") (pin "1") (pinfunction "1_1") (pintype "passive"))
      (node (ref "U4") (pin "7") (pinfunction "OUT_7") (pintype "output"))
      (node (ref "VR16") (pin "E") (pinfunction "E_E") (pintype "passive"))
    )
    (net (code "71") (name "Net-(U4C-+IN)") (class "Default")
      (node (ref "R20") (pin "2") (pinfunction "2_2") (pintype "passive"))
      (node (ref "U4") (pin "10") (pinfunction "+IN_10") (pintype "input"))
    )
    (net (code "72") (name "Net-(U4C--IN)") (class "Default")
      (node (ref "C11") (pin "2") (pinfunction "2_2") (pintype "passive"))
      (node (ref "U4") (pin "9") (pinfunction "-IN_9") (pintype "input"))
      (node (ref "VR3") (pin "E") (pinfunction "E_E") (pintype "passive"))
    )
    (net (code "73") (name "Net-(U4C-OUT)") (class "Default")
      (node (ref "C12") (pin "2") (pinfunction "2_2") (pintype "passive"))
      (node (ref "R22") (pin "1") (pinfunction "1_1") (pintype "passive"))
      (node (ref "U4") (pin "8") (pinfunction "OUT_8") (pintype "output"))
      (node (ref "VR4") (pin "E") (pinfunction "E_E") (pintype "passive"))
    )
    (net (code "74") (name "Net-(U4D-+IN)") (class "Default")
      (node (ref "C5") (pin "1") (pinfunction "1_1") (pintype "passive"))
      (node (ref "R9") (pin "2") (pinfunction "2_2") (pintype "passive"))
      (node (ref "U4") (pin "12") (pinfunction "+IN_12") (pintype "input"))
    )
    (net (code "75") (name "Net-(U4D--IN)") (class "Default")
      (node (ref "C6") (pin "1") (pinfunction "1_1") (pintype "passive"))
      (node (ref "R10") (pin "1") (pinfunction "1_1") (pintype "passive"))
      (node (ref "U4") (pin "13") (pinfunction "-IN_13") (pintype "input"))
    )
    (net (code "76") (name "Net-(U4D-OUT)") (class "Default")
      (node (ref "C4") (pin "2") (pinfunction "2_2") (pintype "passive"))
      (node (ref "C6") (pin "2") (pinfunction "2_2") (pintype "passive"))
      (node (ref "R10") (pin "2") (pinfunction "2_2") (pintype "passive"))
      (node (ref "R11") (pin "1") (pinfunction "1_1") (pintype "passive"))
      (node (ref "U4") (pin "14") (pinfunction "OUT_14") (pintype "output"))
    )
    (net (code "77") (name "Net-(U5A-+IN)") (class "Default")
      (node (ref "R21") (pin "2") (pinfunction "2_2") (pintype "passive"))
      (node (ref "U5") (pin "3") (pinfunction "+IN_3") (pintype "input"))
    )
    (net (code "78") (name "Net-(U5A--IN)") (class "Default")
      (node (ref "C14") (pin "2") (pinfunction "2_2") (pintype "passive"))
      (node (ref "U5") (pin "2") (pinfunction "-IN_2") (pintype "input"))
      (node (ref "VR5") (pin "E") (pinfunction "E_E") (pintype "passive"))
    )
    (net (code "79") (name "Net-(U5A-OUT)") (class "Default")
      (node (ref "C15") (pin "2") (pinfunction "2_2") (pintype "passive"))
      (node (ref "R23") (pin "1") (pinfunction "1_1") (pintype "passive"))
      (node (ref "U5") (pin "1") (pinfunction "OUT_1") (pintype "output"))
      (node (ref "VR6") (pin "E") (pinfunction "E_E") (pintype "passive"))
    )
    (net (code "80") (name "Net-(U5B-+IN)") (class "Default")
      (node (ref "R45") (pin "2") (pinfunction "2_2") (pintype "passive"))
      (node (ref "U5") (pin "5") (pinfunction "+IN_5") (pintype "input"))
    )
    (net (code "81") (name "Net-(U5B--IN)") (class "Default")
      (node (ref "C29") (pin "2") (pinfunction "2_2") (pintype "passive"))
      (node (ref "U5") (pin "6") (pinfunction "-IN_6") (pintype "input"))
      (node (ref "VR13") (pin "E") (pinfunction "E_E") (pintype "passive"))
    )
    (net (code "82") (name "Net-(U5B-OUT)") (class "Default")
      (node (ref "C30") (pin "2") (pinfunction "2_2") (pintype "passive"))
      (node (ref "R49") (pin "1") (pinfunction "1_1") (pintype "passive"))
      (node (ref "U5") (pin "7") (pinfunction "OUT_7") (pintype "output"))
      (node (ref "VR14") (pin "E") (pinfunction "E_E") (pintype "passive"))
    )
    (net (code "83") (name "Net-(U16A-+IN)") (class "Default")
      (node (ref "R65") (pin "1") (pinfunction "1_1") (pintype "passive"))
      (node (ref "U16") (pin "3") (pinfunction "+IN_3") (pintype "input"))
    )
    (net (code "84") (name "Net-(U16A-OUT)") (class "Default")
      (node (ref "C20") (pin "2") (pinfunction "2_2") (pintype "passive"))
      (node (ref "C36") (pin "1") (pinfunction "1_1") (pintype "passive"))
      (node (ref "R61") (pin "1") (pinfunction "1_1") (pintype "passive"))
      (node (ref "U16") (pin "1") (pinfunction "OUT_1") (pintype "output"))
    )
    (net (code "85") (name "Net-(U16B-+IN)") (class "Default")
      (node (ref "R66") (pin "1") (pinfunction "1_1") (pintype "passive"))
      (node (ref "U16") (pin "5") (pinfunction "+IN_5") (pintype "input"))
    )
    (net (code "86") (name "Net-(U16B--IN)") (class "Default")
      (node (ref "C37") (pin "1") (pinfunction "1_1") (pintype "passive"))
      (node (ref "R62") (pin "1") (pinfunction "1_1") (pintype "passive"))
      (node (ref "R63") (pin "2") (pinfunction "2_2") (pintype "passive"))
      (node (ref "R64") (pin "2") (pinfunction "2_2") (pintype "passive"))
      (node (ref "U16") (pin "6") (pinfunction "-IN_6") (pintype "input"))
    )
    (net (code "87") (name "Net-(U16B-OUT)") (class "Default")
      (node (ref "C37") (pin "2") (pinfunction "2_2") (pintype "passive"))
      (node (ref "R63") (pin "1") (pinfunction "1_1") (pintype "passive"))
      (node (ref "R64") (pin "1") (pinfunction "1_1") (pintype "passive"))
      (node (ref "R67") (pin "2") (pinfunction "2_2") (pintype "passive"))
      (node (ref "U16") (pin "7") (pinfunction "OUT_7") (pintype "output"))
    )
    (net (code "88") (name "Net-(VR1.4KA-S)") (class "Default")
      (node (ref "R57") (pin "2") (pinfunction "2_2") (pintype "passive"))
      (node (ref "VR1.4K") (pin "2") (pinfunction "S_2") (pintype "passive"))
    )
    (net (code "89") (name "Net-(VR1.4KB-A)") (class "Default")
      (node (ref "R75") (pin "1") (pinfunction "1_1") (pintype "passive"))
      (node (ref "VR1.4K") (pin "B") (pinfunction "A_B") (pintype "passive"))
    )
    (net (code "90") (name "Net-(VR1KA-S)") (class "Default")
      (node (ref "R56") (pin "2") (pinfunction "2_2") (pintype "passive"))
      (node (ref "VR1K") (pin "2") (pinfunction "S_2") (pintype "passive"))
    )
    (net (code "91") (name "Net-(VR1KB-A)") (class "Default")
      (node (ref "R74") (pin "1") (pinfunction "1_1") (pintype "passive"))
      (node (ref "VR1K") (pin "B") (pinfunction "A_B") (pintype "passive"))
    )
    (net (code "92") (name "Net-(VR2KA-S)") (class "Default")
      (node (ref "R58") (pin "2") (pinfunction "2_2") (pintype "passive"))
      (node (ref "VR2K") (pin "2") (pinfunction "S_2") (pintype "passive"))
    )
    (net (code "93") (name "Net-(VR2KB-A)") (class "Default")
      (node (ref "R76") (pin "1") (pinfunction "1_1") (pintype "passive"))
      (node (ref "VR2K") (pin "B") (pinfunction "A_B") (pintype "passive"))
    )
    (net (code "94") (name "Net-(VR3.5KA-S)") (class "Default")
      (node (ref "R59") (pin "2") (pinfunction "2_2") (pintype "passive"))
      (node (ref "VR3.5K") (pin "2") (pinfunction "S_2") (pintype "passive"))
    )
    (net (code "95") (name "Net-(VR3.5KB-A)") (class "Default")
      (node (ref "R77") (pin "1") (pinfunction "1_1") (pintype "passive"))
      (node (ref "VR3.5K") (pin "B") (pinfunction "A_B") (pintype "passive"))
    )
    (net (code "96") (name "Net-(VR7KA-S)") (class "Default")
      (node (ref "R60") (pin "2") (pinfunction "2_2") (pintype "passive"))
      (node (ref "VR7K") (pin "2") (pinfunction "S_2") (pintype "passive"))
    )
    (net (code "97") (name "Net-(VR7KB-A)") (class "Default")
      (node (ref "R78") (pin "1") (pinfunction "1_1") (pintype "passive"))
      (node (ref "VR7K") (pin "B") (pinfunction "A_B") (pintype "passive"))
    )
    (net (code "98") (name "Net-(VR100A-S)") (class "Default")
      (node (ref "R51") (pin "2") (pinfunction "2_2") (pintype "passive"))
      (node (ref "VR100") (pin "2") (pinfunction "S_2") (pintype "passive"))
    )
    (net (code "99") (name "Net-(VR100B-A)") (class "Default")
      (node (ref "R69") (pin "1") (pinfunction "1_1") (pintype "passive"))
      (node (ref "VR100") (pin "B") (pinfunction "A_B") (pintype "passive"))
    )
    (net (code "100") (name "Net-(VR200A-S)") (class "Default")
      (node (ref "R52") (pin "2") (pinfunction "2_2") (pintype "passive"))
      (node (ref "VR200") (pin "2") (pinfunction "S_2") (pintype "passive"))
    )
    (net (code "101") (name "Net-(VR200B-A)") (class "Default")
      (node (ref "R70") (pin "1") (pinfunction "1_1") (pintype "passive"))
      (node (ref "VR200") (pin "B") (pinfunction "A_B") (pintype "passive"))
    )
    (net (code "102") (name "Net-(VR350A-S)") (class "Default")
      (node (ref "R53") (pin "2") (pinfunction "2_2") (pintype "passive"))
      (node (ref "VR350") (pin "2") (pinfunction "S_2") (pintype "passive"))
    )
    (net (code "103") (name "Net-(VR350B-A)") (class "Default")
      (node (ref "R71") (pin "1") (pinfunction "1_1") (pintype "passive"))
      (node (ref "VR350") (pin "B") (pinfunction "A_B") (pintype "passive"))
    )
    (net (code "104") (name "Net-(VR500A-S)") (class "Default")
      (node (ref "R54") (pin "2") (pinfunction "2_2") (pintype "passive"))
      (node (ref "VR500") (pin "2") (pinfunction "S_2") (pintype "passive"))
    )
    (net (code "105") (name "Net-(VR500B-A)") (class "Default")
      (node (ref "R72") (pin "1") (pinfunction "1_1") (pintype "passive"))
      (node (ref "VR500") (pin "B") (pinfunction "A_B") (pintype "passive"))
    )
    (net (code "106") (name "Net-(VR700A-S)") (class "Default")
      (node (ref "R55") (pin "2") (pinfunction "2_2") (pintype "passive"))
      (node (ref "VR700") (pin "2") (pinfunction "S_2") (pintype "passive"))
    )
    (net (code "107") (name "Net-(VR700B-A)") (class "Default")
      (node (ref "R73") (pin "1") (pinfunction "1_1") (pintype "passive"))
      (node (ref "VR700") (pin "B") (pinfunction "A_B") (pintype "passive"))
    )
    (net (code "108") (name "VCC") (class "Default")
      (node (ref "C39") (pin "+") (pinfunction "+_+") (pintype "passive"))
      (node (ref "C41") (pin "+") (pinfunction "+_+") (pintype "passive"))
      (node (ref "C43") (pin "1") (pinfunction "1_1") (pintype "passive"))
      (node (ref "C45") (pin "1") (pinfunction "1_1") (pintype "passive"))
      (node (ref "C47") (pin "1") (pinfunction "1_1") (pintype "passive"))
      (node (ref "C49") (pin "1") (pinfunction "1_1") (pintype "passive"))
      (node (ref "C51") (pin "1") (pinfunction "1_1") (pintype "passive"))
      (node (ref "D2") (pin "C") (pinfunction "C_C") (pintype "passive"))
      (node (ref "R69") (pin "2") (pinfunction "2_2") (pintype "passive"))
      (node (ref "R70") (pin "2") (pinfunction "2_2") (pintype "passive"))
      (node (ref "R71") (pin "2") (pinfunction "2_2") (pintype "passive"))
      (node (ref "R72") (pin "2") (pinfunction "2_2") (pintype "passive"))
      (node (ref "R73") (pin "2") (pinfunction "2_2") (pintype "passive"))
      (node (ref "R74") (pin "2") (pinfunction "2_2") (pintype "passive"))
      (node (ref "R75") (pin "2") (pinfunction "2_2") (pintype "passive"))
      (node (ref "R76") (pin "2") (pinfunction "2_2") (pintype "passive"))
      (node (ref "R77") (pin "2") (pinfunction "2_2") (pintype "passive"))
      (node (ref "R78") (pin "2") (pinfunction "2_2") (pintype "passive"))
      (node (ref "U16") (pin "8") (pinfunction "V+_8") (pintype "power_in"))
      (node (ref "U2") (pin "8") (pinfunction "V+_8") (pintype "power_in"))
      (node (ref "U3") (pin "4") (pinfunction "V+_4") (pintype "power_in"))
      (node (ref "U4") (pin "4") (pinfunction "V+_4") (pintype "power_in"))
      (node (ref "U5") (pin "8") (pinfunction "V+_8") (pintype "power_in"))
    )
    (net (code "109") (name "VEE") (class "Default")
      (node (ref "C38") (pin "-") (pinfunction "-_-") (pintype "passive"))
      (node (ref "C40") (pin "-") (pinfunction "-_-") (pintype "passive"))
      (node (ref "C42") (pin "2") (pinfunction "2_2") (pintype "passive"))
      (node (ref "C44") (pin "2") (pinfunction "2_2") (pintype "passive"))
      (node (ref "C46") (pin "2") (pinfunction "2_2") (pintype "passive"))
      (node (ref "C48") (pin "2") (pinfunction "2_2") (pintype "passive"))
      (node (ref "C50") (pin "2") (pinfunction "2_2") (pintype "passive"))
      (node (ref "D1") (pin "A") (pinfunction "A_A") (pintype "passive"))
      (node (ref "U16") (pin "4") (pinfunction "V-_4") (pintype "power_in"))
      (node (ref "U2") (pin "4") (pinfunction "V-_4") (pintype "power_in"))
      (node (ref "U3") (pin "11") (pinfunction "V-_11") (pintype "power_in"))
      (node (ref "U4") (pin "11") (pinfunction "V-_11") (pintype "power_in"))
      (node (ref "U5") (pin "4") (pinfunction "V-_4") (pintype "power_in"))
    )
    (net (code "110") (name "unconnected-(1.4K-SWITCH-PadP$2_SWITCH)") (class "Default")
      (node (ref "1.4K") (pin "P$2_SWITCH") (pinfunction "SWITCH_P$2_SWITCH") (pintype "passive"))
    )
    (net (code "111") (name "unconnected-(1K-SWITCH-PadP$2_SWITCH)") (class "Default")
      (node (ref "1K") (pin "P$2_SWITCH") (pinfunction "SWITCH_P$2_SWITCH") (pintype "passive"))
    )
    (net (code "112") (name "unconnected-(2K-SWITCH-PadP$2_SWITCH)") (class "Default")
      (node (ref "2K") (pin "P$2_SWITCH") (pinfunction "SWITCH_P$2_SWITCH") (pintype "passive"))
    )
    (net (code "113") (name "unconnected-(3.5K-SWITCH-PadP$2_SWITCH)") (class "Default")
      (node (ref "3.5K") (pin "P$2_SWITCH") (pinfunction "SWITCH_P$2_SWITCH") (pintype "passive"))
    )
    (net (code "114") (name "unconnected-(200-SWITCH-PadP$2_SWITCH)") (class "Default")
      (node (ref "200") (pin "P$2_SWITCH") (pinfunction "SWITCH_P$2_SWITCH") (pintype "passive"))
    )
    (net (code "115") (name "unconnected-(350-SWITCH-PadP$2_SWITCH)") (class "Default")
      (node (ref "350") (pin "P$2_SWITCH") (pinfunction "SWITCH_P$2_SWITCH") (pintype "passive"))
    )
    (net (code "116") (name "unconnected-(500-SWITCH-PadP$2_SWITCH)") (class "Default")
      (node (ref "500") (pin "P$2_SWITCH") (pinfunction "SWITCH_P$2_SWITCH") (pintype "passive"))
    )
    (net (code "117") (name "unconnected-(700-SWITCH-PadP$2_SWITCH)") (class "Default")
      (node (ref "700") (pin "P$2_SWITCH") (pinfunction "SWITCH_P$2_SWITCH") (pintype "passive"))
    )
    (net (code "118") (name "unconnected-(<100-SWITCH-PadP$2_SWITCH)") (class "Default")
      (node (ref "<100") (pin "P$2_SWITCH") (pinfunction "SWITCH_P$2_SWITCH") (pintype "passive"))
    )
    (net (code "119") (name "unconnected-(>7K-SWITCH-PadP$2_SWITCH)") (class "Default")
      (node (ref ">7K") (pin "P$2_SWITCH") (pinfunction "SWITCH_P$2_SWITCH") (pintype "passive"))
    )
    (net (code "120") (name "unconnected-(SUM_OUT-SWITCH-PadP$2_SWITCH)") (class "Default")
      (node (ref "SUM_OUT") (pin "P$2_SWITCH") (pinfunction "SWITCH_P$2_SWITCH") (pintype "passive"))
    )
    (net (code "121") (name "unconnected-(VR1-PadA)") (class "Default")
      (node (ref "VR1") (pin "A") (pinfunction "A_A") (pintype "passive"))
    )
    (net (code "122") (name "unconnected-(VR3-PadA)") (class "Default")
      (node (ref "VR3") (pin "A") (pinfunction "A_A") (pintype "passive"))
    )
    (net (code "123") (name "unconnected-(VR5-PadA)") (class "Default")
      (node (ref "VR5") (pin "A") (pinfunction "A_A") (pintype "passive"))
    )
    (net (code "124") (name "unconnected-(VR7-PadA)") (class "Default")
      (node (ref "VR7") (pin "A") (pinfunction "A_A") (pintype "passive"))
    )
    (net (code "125") (name "unconnected-(VR9-PadA)") (class "Default")
      (node (ref "VR9") (pin "A") (pinfunction "A_A") (pintype "passive"))
    )
    (net (code "126") (name "unconnected-(VR11-PadA)") (class "Default")
      (node (ref "VR11") (pin "A") (pinfunction "A_A") (pintype "passive"))
    )
    (net (code "127") (name "unconnected-(VR13-PadA)") (class "Default")
      (node (ref "VR13") (pin "A") (pinfunction "A_A") (pintype "passive"))
    )
    (net (code "128") (name "unconnected-(VR15-PadA)") (class "Default")
      (node (ref "VR15") (pin "A") (pinfunction "A_A") (pintype "passive"))
    )
  )
)
